# Assignment_1.net
KiCad netlist of a schematic drawn in Altium Designer
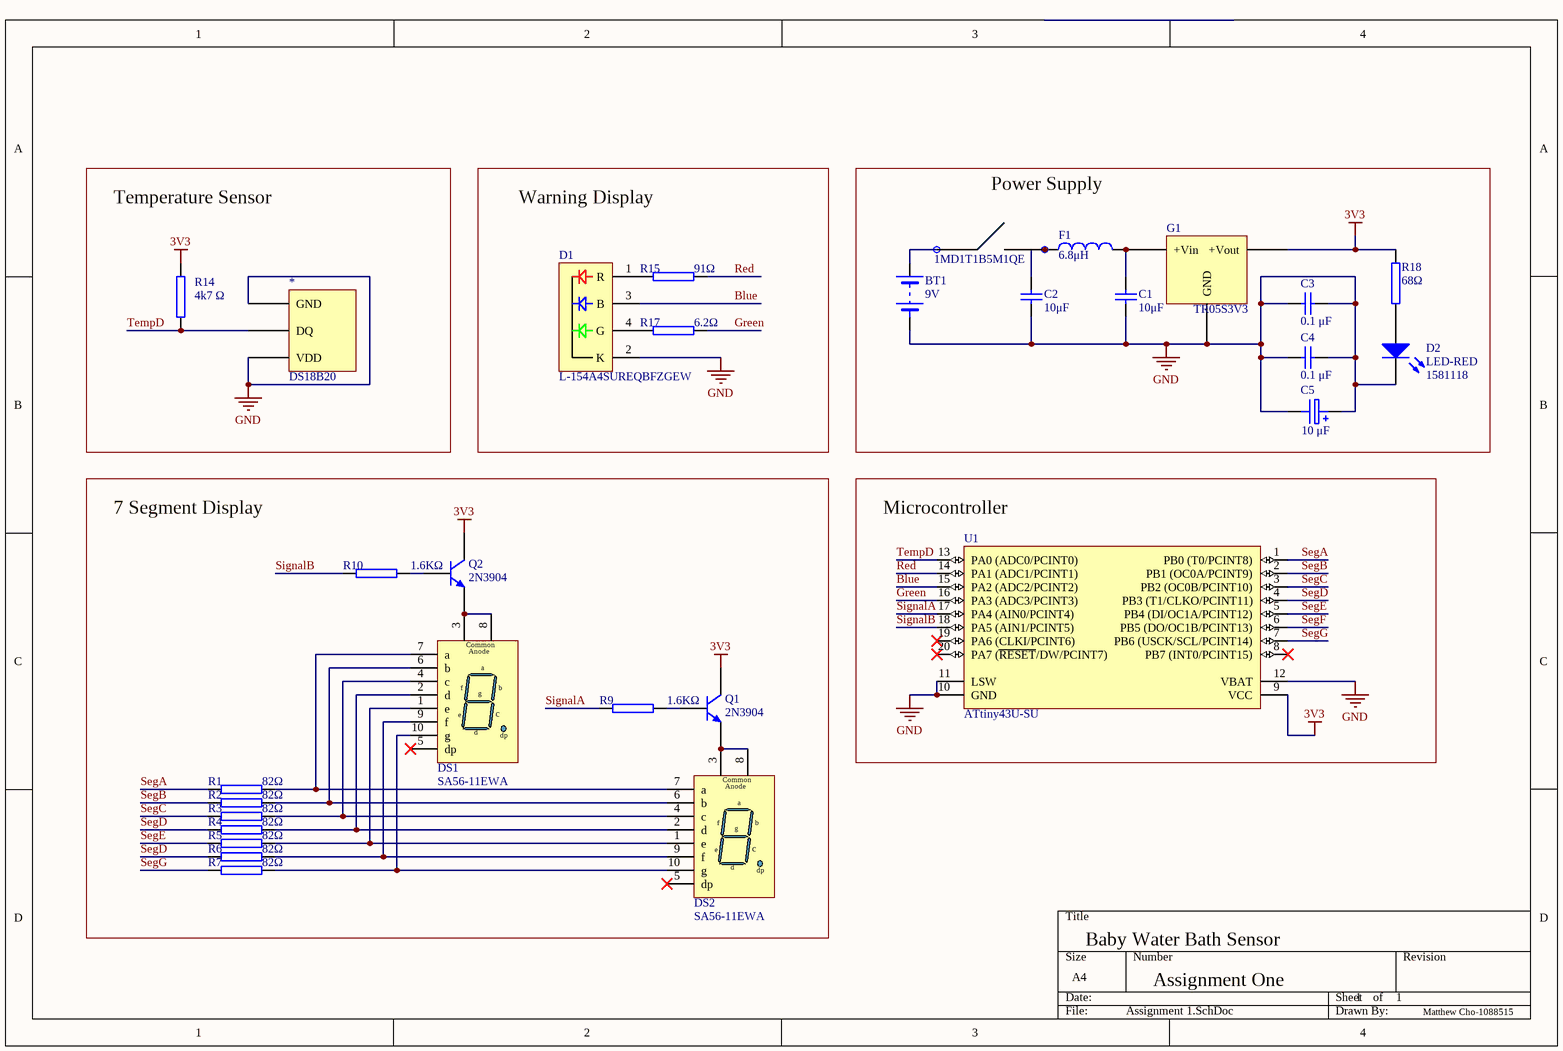
[diagram p0: Assignment 1.SchDoc]

(export (version "E")
  (design (tool "Eeschema 10.0.6"))
  (components
    (comp (ref "*") (value "DS18B20") (libsource (lib "WaterTemp1wirepin") (part "DS18B20")))
    (comp (ref "BT1")
      (value "9V")
      (footprint "BAT-1_AUT")
      (description "Multicell Batterry")
      (libsource (lib "Standards") (part "Battery2"))
    )
    (comp (ref "C1")
      (value "10μF")
      (footprint "CAP_0805")
      (description "Non Polarized Capacitor, SMD, 0805")
      (libsource (lib "Resistors and Capacitors") (part "CAPN 0805"))
    )
    (comp (ref "C2")
      (value "10μF")
      (footprint "CAP_0805")
      (description "Non Polarized Capacitor, SMD, 0805")
      (libsource (lib "Resistors and Capacitors") (part "CAPN 0805"))
    )
    (comp (ref "C3")
      (value "0.1 μF")
      (footprint "CAP_1210")
      (description "Non Polarized Capacitor, SMD, 1210")
      (libsource (lib "Resistors and Capacitors") (part "CAPN 1210"))
    )
    (comp (ref "C4")
      (value "0.1 μF")
      (footprint "CAP_1210")
      (description "Non Polarized Capacitor, SMD, 1210")
      (libsource (lib "Resistors and Capacitors") (part "CAPN 1210"))
    )
    (comp (ref "C5")
      (value "10 μF")
      (footprint "CAPP100-200_AUT")
      (description "Polarized Aluminum Capacitor, Through Hole, Pitch 100mil, Body 200mil (Dia)")
      (libsource (lib "Resistors and Capacitors") (part "CAPP100-200"))
    )
    (comp (ref "D1")
      (value "L-154A4SUREQBFZGEW")
      (footprint "LED 5mm_RGB")
      (description "KINGBRIGHT - L-154A4SUREQBFZGEW - LED, MULTICOL., RGB 5MM, X-BRIGHT")
      (libsource (lib "LEDs") (part "5mm LED-RGB"))
    )
    (comp (ref "D2")
      (value "LED-RED")
      (footprint "LED3MM_R_AUT")
      (description "3mm RED LED, Through Hole")
      (fields (field (name "SUPPLIER PART NUMBER 1") "1581118"))
      (libsource (lib "LEDs") (part "3mm LED-RED"))
    )
    (comp (ref "DS1")
      (value "SA56-11EWA")
      (footprint "DISP-7SEG/14.2_AUT")
      (description "14.2 mm General Purpose 7-Segment Display: CA, RH DP, Gray Surface.")
      (libsource (lib "Display") (part "Display-CA/14.2 (7-Segment Display)"))
    )
    (comp (ref "DS2")
      (value "SA56-11EWA")
      (footprint "DISP-7SEG/14.2_AUT")
      (description "14.2 mm General Purpose 7-Segment Display: CA, RH DP, Gray Surface.")
      (libsource (lib "Display") (part "Display-CA/14.2 (7-Segment Display)"))
    )
    (comp (ref "F1")
      (value "6.8μH")
      (footprint "0805")
      (description "Choke, 2A,  600ohm at 100MHz")
      (libsource (lib "Inductors and Chokes") (part "MLB-201209-0600PN"))
    )
    (comp (ref "G1") (value "TR05S3V3") (libsource (lib "VoltageRegS3V3") (part "TR05S3V3")))
    (comp (ref "P1") (value "1MD1T1B5M1QE") (libsource (lib "Switch") (part "1MD1T1B5M1QE")))
    (comp (ref "Q1")
      (value "2N3904")
      (footprint "TO-92AUT")
      (description "NPN General Purpose Amplifier, 40v, 200mA, 250MHz")
      (libsource (lib "Transistors and FETs") (part "2N3904"))
    )
    (comp (ref "Q2")
      (value "2N3904")
      (footprint "TO-92AUT")
      (description "NPN General Purpose Amplifier, 40v, 200mA, 250MHz")
      (libsource (lib "Transistors and FETs") (part "2N3904"))
    )
    (comp (ref "R1")
      (value "82Ω")
      (footprint "AXIAL-0.5AUT")
      (description "Resistor, Through Hole, Pitch 500mil")
      (libsource (lib "Resistors and Capacitors") (part "Resistor 1/2W"))
    )
    (comp (ref "R2")
      (value "82Ω")
      (footprint "AXIAL-0.5AUT")
      (description "Resistor, Through Hole, Pitch 500mil")
      (libsource (lib "Resistors and Capacitors") (part "Resistor 1/2W"))
    )
    (comp (ref "R3")
      (value "82Ω")
      (footprint "AXIAL-0.5AUT")
      (description "Resistor, Through Hole, Pitch 500mil")
      (libsource (lib "Resistors and Capacitors") (part "Resistor 1/2W"))
    )
    (comp (ref "R4")
      (value "82Ω")
      (footprint "AXIAL-0.5AUT")
      (description "Resistor, Through Hole, Pitch 500mil")
      (libsource (lib "Resistors and Capacitors") (part "Resistor 1/2W"))
    )
    (comp (ref "R5")
      (value "82Ω")
      (footprint "AXIAL-0.5AUT")
      (description "Resistor, Through Hole, Pitch 500mil")
      (libsource (lib "Resistors and Capacitors") (part "Resistor 1/2W"))
    )
    (comp (ref "R6")
      (value "82Ω")
      (footprint "AXIAL-0.5AUT")
      (description "Resistor, Through Hole, Pitch 500mil")
      (libsource (lib "Resistors and Capacitors") (part "Resistor 1/2W"))
    )
    (comp (ref "R7")
      (value "82Ω")
      (footprint "AXIAL-0.5AUT")
      (description "Resistor, Through Hole, Pitch 500mil")
      (libsource (lib "Resistors and Capacitors") (part "Resistor 1/2W"))
    )
    (comp (ref "R9")
      (value "1.6KΩ")
      (footprint "AXIAL-0.5AUT")
      (description "Resistor, Through Hole, Pitch 500mil")
      (libsource (lib "Resistors and Capacitors") (part "Resistor 1/2W"))
    )
    (comp (ref "R10")
      (value "1.6KΩ")
      (footprint "AXIAL-0.5AUT")
      (description "Resistor, Through Hole, Pitch 500mil")
      (libsource (lib "Resistors and Capacitors") (part "Resistor 1/2W"))
    )
    (comp (ref "R14")
      (value "4k7 Ω")
      (footprint "AXIAL-0.5AUT")
      (description "Resistor, Through Hole, Pitch 500mil")
      (libsource (lib "Resistors and Capacitors") (part "Resistor 1/2W"))
    )
    (comp (ref "R15")
      (value "91Ω")
      (footprint "AXIAL-0.5AUT")
      (description "Resistor, Through Hole, Pitch 500mil")
      (libsource (lib "Resistors and Capacitors") (part "Resistor 1/2W"))
    )
    (comp (ref "R17")
      (value "6.2Ω")
      (footprint "AXIAL-0.5AUT")
      (description "Resistor, Through Hole, Pitch 500mil")
      (libsource (lib "Resistors and Capacitors") (part "Resistor 1/2W"))
    )
    (comp (ref "R18")
      (value "68Ω")
      (footprint "AXIAL-0.5AUT")
      (description "Resistor, Through Hole, Pitch 500mil")
      (libsource (lib "Resistors and Capacitors") (part "Resistor 1/2W"))
    )
    (comp (ref "U1")
      (value "ATtiny43U-SU")
      (footprint "20S2_M")
      (fields (field (name "PUBLISHER") "Altium Limited"))
      (libsource (lib "Atmel_Tiny_Micro") (part "ATtiny43U-SU"))
    )
  )
  (nets
    (net (code "1") (name "/Blue") (class "Default")
      (node (ref "D1") (pin "3") (pinfunction "B_3") (pintype "passive"))
      (node (ref "U1") (pin "15") (pinfunction "PA2_(ADC2/PCINT2)_15") (pintype "bidirectional"))
    )
    (net (code "2") (name "/Green") (class "Default")
      (node (ref "R17") (pin "2") (pinfunction "2_2") (pintype "passive"))
      (node (ref "U1") (pin "16") (pinfunction "PA3_(ADC3/PCINT3)_16") (pintype "bidirectional"))
    )
    (net (code "3") (name "/Red") (class "Default")
      (node (ref "R15") (pin "2") (pinfunction "2_2") (pintype "passive"))
      (node (ref "U1") (pin "14") (pinfunction "PA1_(ADC1/PCINT1)_14") (pintype "bidirectional"))
    )
    (net (code "4") (name "/SegA") (class "Default")
      (node (ref "R1") (pin "1") (pinfunction "1_1") (pintype "passive"))
      (node (ref "U1") (pin "1") (pinfunction "PB0_(T0/PCINT8)_1") (pintype "bidirectional"))
    )
    (net (code "5") (name "/SegB") (class "Default")
      (node (ref "R2") (pin "1") (pinfunction "1_1") (pintype "passive"))
      (node (ref "U1") (pin "2") (pinfunction "PB1_(OC0A/PCINT9)_2") (pintype "bidirectional"))
    )
    (net (code "6") (name "/SegC") (class "Default")
      (node (ref "R3") (pin "1") (pinfunction "1_1") (pintype "passive"))
      (node (ref "U1") (pin "3") (pinfunction "PB2_(OC0B/PCINT10)_3") (pintype "bidirectional"))
    )
    (net (code "7") (name "/SegD") (class "Default")
      (node (ref "R4") (pin "1") (pinfunction "1_1") (pintype "passive"))
      (node (ref "R6") (pin "1") (pinfunction "1_1") (pintype "passive"))
      (node (ref "U1") (pin "4") (pinfunction "PB3_(T1/CLKO/PCINT11)_4") (pintype "bidirectional"))
    )
    (net (code "8") (name "/SegE") (class "Default")
      (node (ref "R5") (pin "1") (pinfunction "1_1") (pintype "passive"))
      (node (ref "U1") (pin "5") (pinfunction "PB4_(DI/OC1A/PCINT12)_5") (pintype "bidirectional"))
    )
    (net (code "9") (name "/SegF") (class "Default")
      (node (ref "U1") (pin "6") (pinfunction "PB5_(DO/OC1B/PCINT13)_6") (pintype "bidirectional"))
    )
    (net (code "10") (name "/SegG") (class "Default")
      (node (ref "R7") (pin "1") (pinfunction "1_1") (pintype "passive"))
      (node (ref "U1") (pin "7") (pinfunction "PB6_(USCK/SCL/PCINT14)_7") (pintype "bidirectional"))
    )
    (net (code "11") (name "/SignalA") (class "Default")
      (node (ref "R9") (pin "1") (pinfunction "1_1") (pintype "passive"))
      (node (ref "U1") (pin "17") (pinfunction "PA4_(AIN0/PCINT4)_17") (pintype "bidirectional"))
    )
    (net (code "12") (name "/SignalB") (class "Default")
      (node (ref "R10") (pin "1") (pinfunction "1_1") (pintype "passive"))
      (node (ref "U1") (pin "18") (pinfunction "PA5_(AIN1/PCINT5)_18") (pintype "bidirectional"))
    )
    (net (code "13") (name "/TempD") (class "Default")
      (node (ref "*") (pin "4") (pinfunction "DQ_4") (pintype "passive"))
      (node (ref "R14") (pin "2") (pinfunction "2_2") (pintype "passive"))
      (node (ref "U1") (pin "13") (pinfunction "PA0_(ADC0/PCINT0)_13") (pintype "bidirectional"))
    )
    (net (code "14") (name "3V3") (class "Default")
      (node (ref "G1") (pin "4") (pinfunction "+Vout_4") (pintype "passive"))
      (node (ref "Q1") (pin "3") (pinfunction "C_3") (pintype "passive"))
      (node (ref "Q2") (pin "3") (pinfunction "C_3") (pintype "passive"))
      (node (ref "R14") (pin "1") (pinfunction "1_1") (pintype "passive"))
      (node (ref "R18") (pin "1") (pinfunction "1_1") (pintype "passive"))
      (node (ref "U1") (pin "9") (pinfunction "VCC_9") (pintype "power_in"))
    )
    (net (code "15") (name "GND") (class "Default")
      (node (ref "*") (pin "3") (pinfunction "VDD_3") (pintype "passive"))
      (node (ref "*") (pin "5") (pinfunction "GND_5") (pintype "passive"))
      (node (ref "BT1") (pin "2") (pintype "passive"))
      (node (ref "C1") (pin "2") (pinfunction "2_2") (pintype "passive"))
      (node (ref "C2") (pin "2") (pinfunction "2_2") (pintype "passive"))
      (node (ref "C3") (pin "1") (pinfunction "1_1") (pintype "passive"))
      (node (ref "C3") (pin "2") (pinfunction "2_2") (pintype "passive"))
      (node (ref "C4") (pin "1") (pinfunction "1_1") (pintype "passive"))
      (node (ref "C4") (pin "2") (pinfunction "2_2") (pintype "passive"))
      (node (ref "C5") (pin "1") (pinfunction "1_1") (pintype "passive"))
      (node (ref "C5") (pin "2") (pinfunction "2_2") (pintype "passive"))
      (node (ref "D1") (pin "2") (pinfunction "K_2") (pintype "passive"))
      (node (ref "D2") (pin "K") (pinfunction "K_K") (pintype "passive"))
      (node (ref "G1") (pin "5") (pinfunction "GND_5") (pintype "passive"))
      (node (ref "U1") (pin "10") (pinfunction "GND_10") (pintype "power_in"))
      (node (ref "U1") (pin "11") (pinfunction "LSW_11") (pintype "passive"))
      (node (ref "U1") (pin "12") (pinfunction "VBAT_12") (pintype "power_in"))
    )
    (net (code "16") (name "Net-(BT1-Pad1)") (class "Default")
      (node (ref "BT1") (pin "1") (pintype "passive"))
      (node (ref "P1") (pin "0") (pinfunction "0_0") (pintype "passive"))
    )
    (net (code "17") (name "Net-(C2-Pad1)") (class "Default")
      (node (ref "C2") (pin "1") (pinfunction "1_1") (pintype "passive"))
      (node (ref "F1") (pin "1") (pinfunction "1_1") (pintype "passive"))
      (node (ref "P1") (pin "0") (pinfunction "0_0") (pintype "passive"))
    )
    (net (code "18") (name "Net-(D1-G)") (class "Default")
      (node (ref "D1") (pin "4") (pinfunction "G_4") (pintype "passive"))
      (node (ref "R17") (pin "1") (pinfunction "1_1") (pintype "passive"))
    )
    (net (code "19") (name "Net-(D1-R)") (class "Default")
      (node (ref "D1") (pin "1") (pinfunction "R_1") (pintype "passive"))
      (node (ref "R15") (pin "1") (pinfunction "1_1") (pintype "passive"))
    )
    (net (code "20") (name "Net-(D2-PadA)") (class "Default")
      (node (ref "D2") (pin "A") (pinfunction "A_A") (pintype "passive"))
      (node (ref "R18") (pin "2") (pinfunction "2_2") (pintype "passive"))
    )
    (net (code "21") (name "Net-(DS1-a)") (class "Default")
      (node (ref "DS1") (pin "7") (pinfunction "a_7") (pintype "passive"))
      (node (ref "DS2") (pin "7") (pinfunction "a_7") (pintype "passive"))
      (node (ref "R1") (pin "2") (pinfunction "2_2") (pintype "passive"))
    )
    (net (code "22") (name "Net-(DS1-b)") (class "Default")
      (node (ref "DS1") (pin "6") (pinfunction "b_6") (pintype "passive"))
      (node (ref "DS2") (pin "6") (pinfunction "b_6") (pintype "passive"))
      (node (ref "R2") (pin "2") (pinfunction "2_2") (pintype "passive"))
    )
    (net (code "23") (name "Net-(DS1-c)") (class "Default")
      (node (ref "DS1") (pin "4") (pinfunction "c_4") (pintype "passive"))
      (node (ref "DS2") (pin "4") (pinfunction "c_4") (pintype "passive"))
      (node (ref "R3") (pin "2") (pinfunction "2_2") (pintype "passive"))
    )
    (net (code "24") (name "Net-(DS1-d)") (class "Default")
      (node (ref "DS1") (pin "2") (pinfunction "d_2") (pintype "passive"))
      (node (ref "DS2") (pin "2") (pinfunction "d_2") (pintype "passive"))
      (node (ref "R4") (pin "2") (pinfunction "2_2") (pintype "passive"))
    )
    (net (code "25") (name "Net-(DS1-e)") (class "Default")
      (node (ref "DS1") (pin "1") (pinfunction "e_1") (pintype "passive"))
      (node (ref "DS2") (pin "1") (pinfunction "e_1") (pintype "passive"))
      (node (ref "R5") (pin "2") (pinfunction "2_2") (pintype "passive"))
    )
    (net (code "26") (name "Net-(DS1-f)") (class "Default")
      (node (ref "DS1") (pin "9") (pinfunction "f_9") (pintype "passive"))
      (node (ref "DS2") (pin "9") (pinfunction "f_9") (pintype "passive"))
      (node (ref "R6") (pin "2") (pinfunction "2_2") (pintype "passive"))
    )
    (net (code "27") (name "Net-(DS1-g)") (class "Default")
      (node (ref "DS1") (pin "10") (pinfunction "g_10") (pintype "passive"))
      (node (ref "DS2") (pin "10") (pinfunction "g_10") (pintype "passive"))
      (node (ref "R7") (pin "2") (pinfunction "2_2") (pintype "passive"))
    )
    (net (code "28") (name "Net-(G1-+Vin)") (class "Default")
      (node (ref "C1") (pin "1") (pinfunction "1_1") (pintype "passive"))
      (node (ref "F1") (pin "2") (pinfunction "2_2") (pintype "passive"))
      (node (ref "G1") (pin "3") (pinfunction "+Vin_3") (pintype "passive"))
    )
    (net (code "29") (name "Net-(Q1-B)") (class "Default")
      (node (ref "Q1") (pin "2") (pinfunction "B_2") (pintype "passive"))
      (node (ref "R9") (pin "2") (pinfunction "2_2") (pintype "passive"))
    )
    (net (code "30") (name "Net-(Q1-E)") (class "Default")
      (node (ref "DS2") (pin "3") (pinfunction "A_3") (pintype "passive"))
      (node (ref "DS2") (pin "8") (pinfunction "A_8") (pintype "passive"))
      (node (ref "Q1") (pin "1") (pinfunction "E_1") (pintype "passive"))
    )
    (net (code "31") (name "Net-(Q2-B)") (class "Default")
      (node (ref "Q2") (pin "2") (pinfunction "B_2") (pintype "passive"))
      (node (ref "R10") (pin "2") (pinfunction "2_2") (pintype "passive"))
    )
    (net (code "32") (name "Net-(Q2-E)") (class "Default")
      (node (ref "DS1") (pin "3") (pinfunction "A_3") (pintype "passive"))
      (node (ref "DS1") (pin "8") (pinfunction "A_8") (pintype "passive"))
      (node (ref "Q2") (pin "1") (pinfunction "E_1") (pintype "passive"))
    )
    (net (code "33") (name "unconnected-(DS1-dp-Pad5)") (class "Default")
      (node (ref "DS1") (pin "5") (pinfunction "dp_5") (pintype "passive+no_connect"))
    )
    (net (code "34") (name "unconnected-(DS2-dp-Pad5)") (class "Default")
      (node (ref "DS2") (pin "5") (pinfunction "dp_5") (pintype "passive+no_connect"))
    )
    (net (code "35") (name "unconnected-(U1-PA6_(CLKI{slash}PCINT6)-Pad19)") (class "Default")
      (node (ref "U1") (pin "19") (pinfunction "PA6_(CLKI/PCINT6)_19") (pintype "bidirectional+no_connect"))
    )
    (net (code "36") (name "unconnected-(U1-PA7_(~{RESET}{slash}DW{slash}PCINT7)-Pad20)") (class "Default")
      (node (ref "U1") (pin "20") (pinfunction "PA7_(~{RESET}/DW/PCINT7)_20") (pintype "bidirectional+no_connect"))
    )
    (net (code "37") (name "unconnected-(U1-PB7_(INT0{slash}PCINT15)-Pad8)") (class "Default")
      (node (ref "U1") (pin "8") (pinfunction "PB7_(INT0/PCINT15)_8") (pintype "bidirectional+no_connect"))
    )
  )
)
